# 03-MCU_INTERFACE.net
KiCad netlist of a schematic drawn in Altium Designer
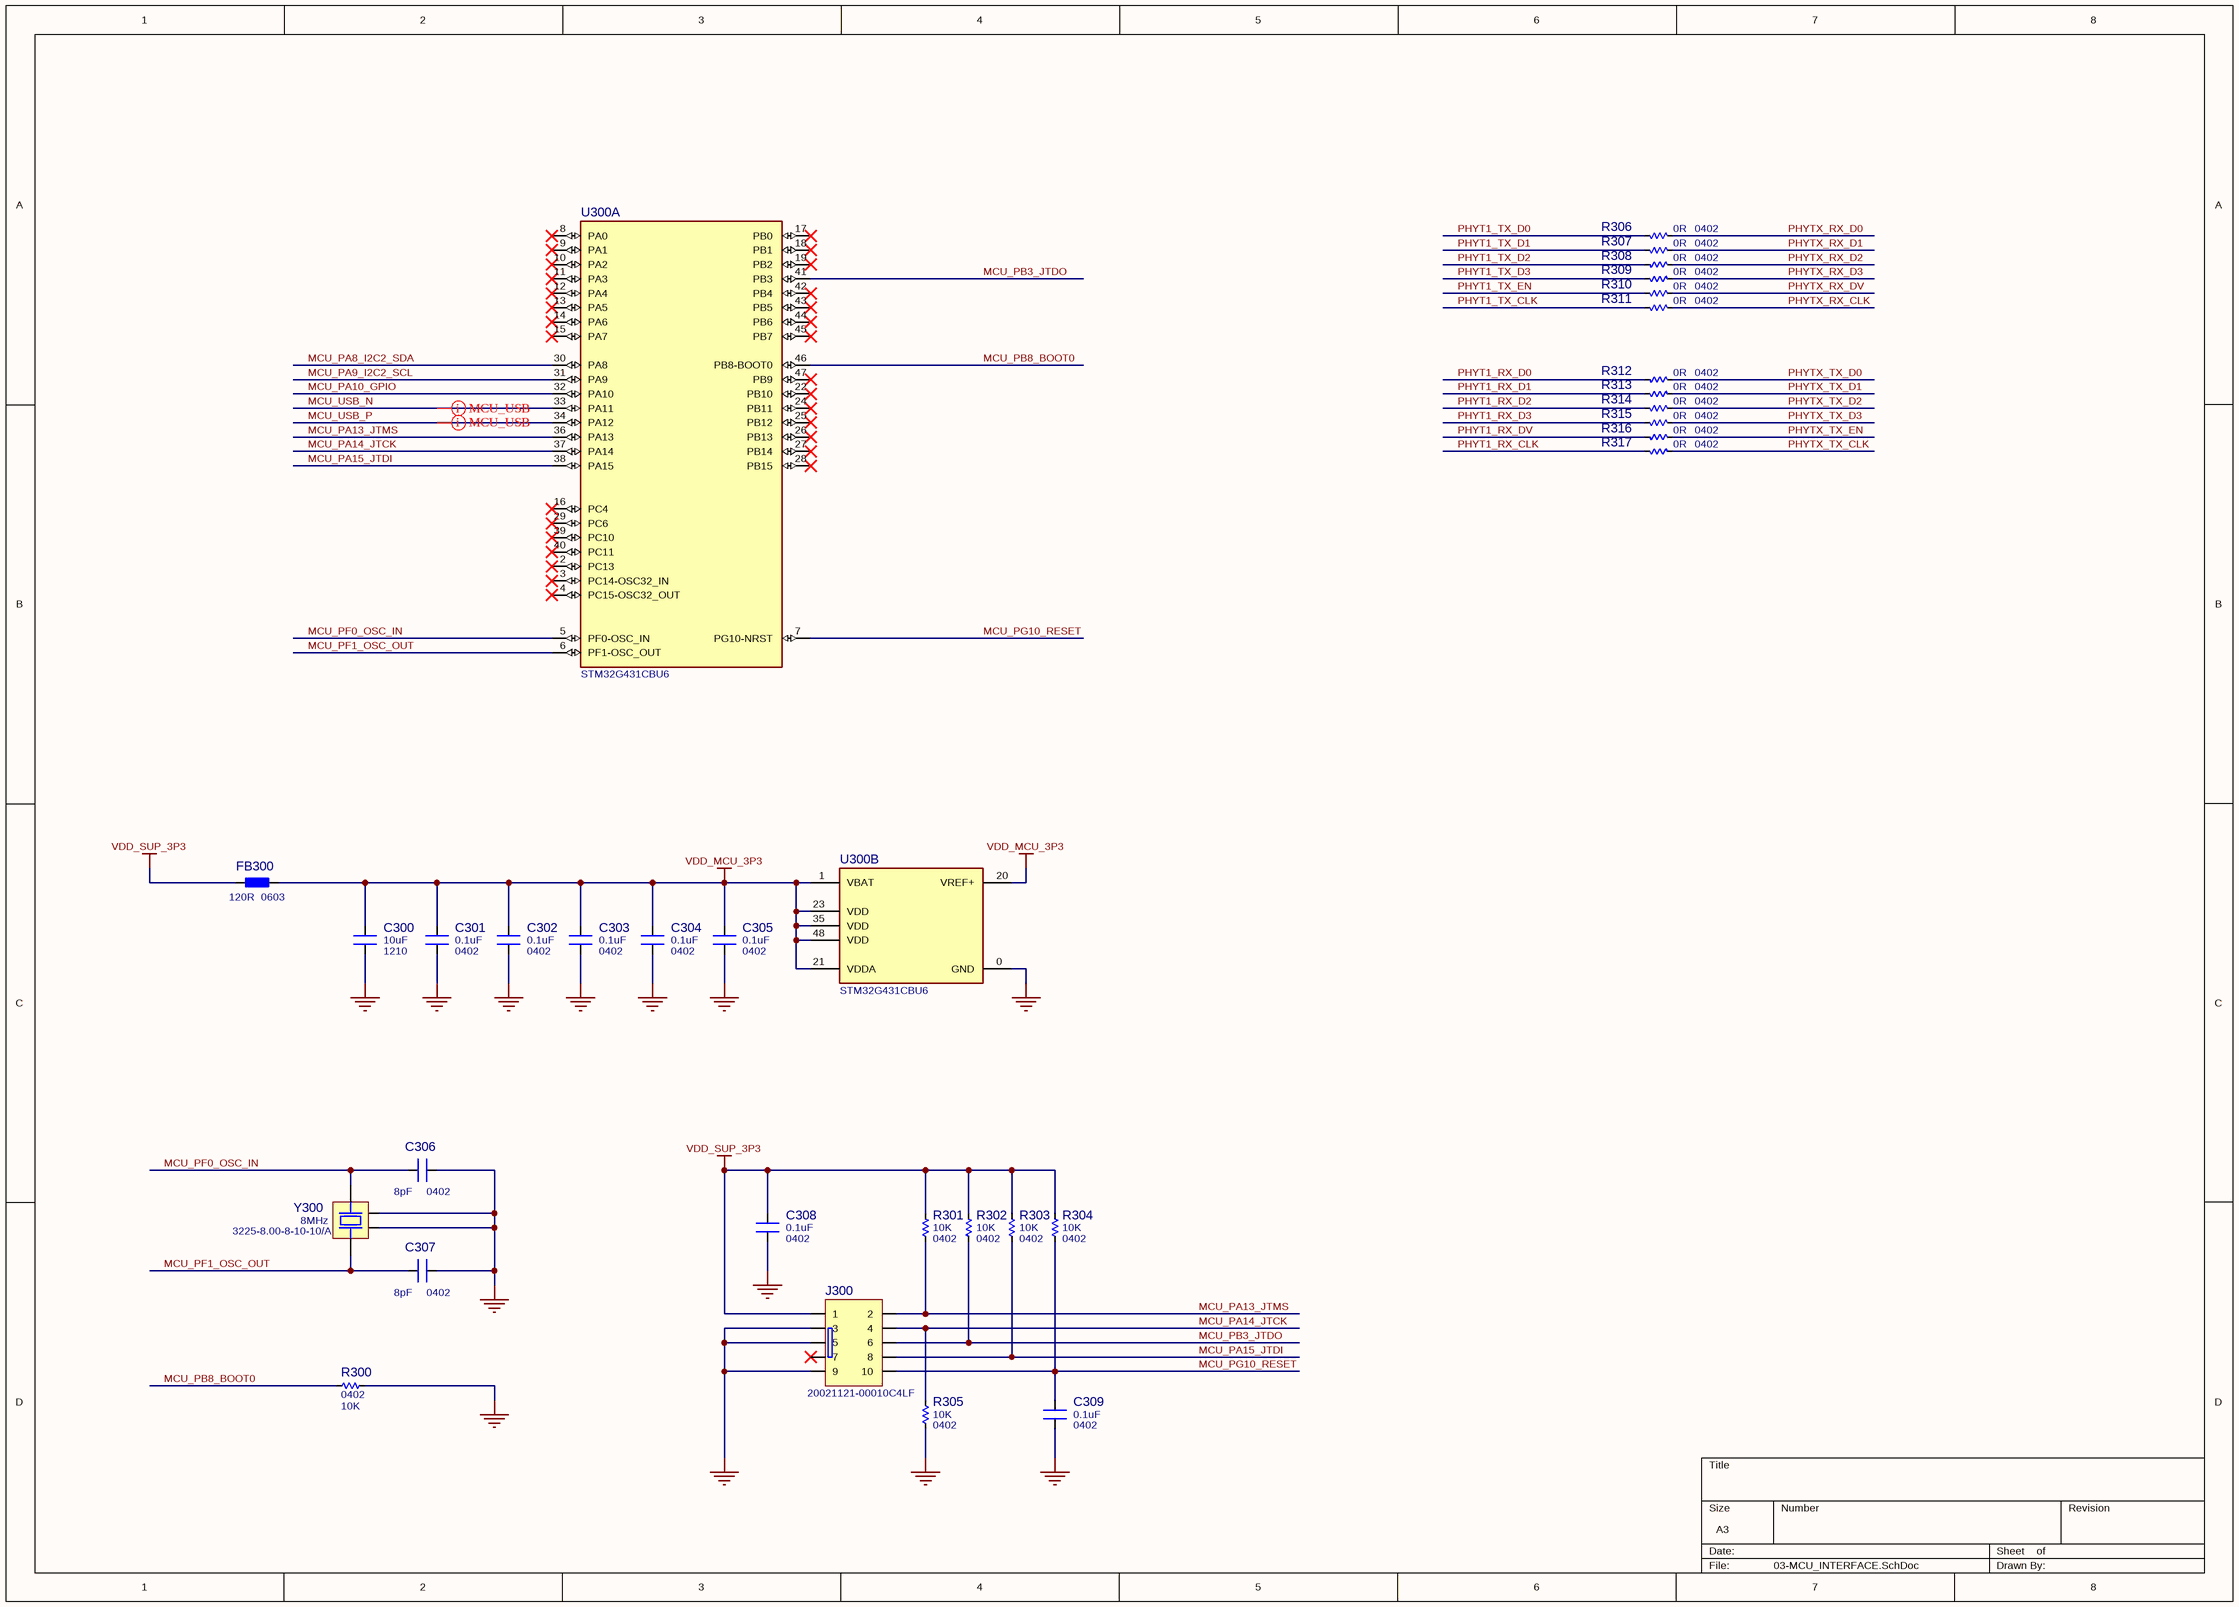
[diagram p0: 03-MCU_INTERFACE.SchDoc]

(export (version "E")
  (design (tool "Eeschema 10.0.6"))
  (components
    (comp (ref "C300")
      (value "10uF")
      (footprint "CAP_C_1210")
      (description "Ceramic Capacitor SMD 1210 10uF ±10% 25V")
      (fields
        (field (name "TOLERANCE") "±10%")
        (field (name "MANUFACTURER") "Samsung")
        (field (name "PACKAGE") "1210")
      )
      (libsource (lib "AS50") (part "Cap"))
    )
    (comp (ref "C301")
      (value "0.1uF")
      (footprint "CAP_C_0402")
      (description "Ceramic Capacitor SMD 0402 100nF ±10% 16V")
      (fields
        (field (name "TOLERANCE") "±10%")
        (field (name "MANUFACTURER") "Samsung")
        (field (name "PACKAGE") "0402")
      )
      (libsource (lib "AS50") (part "Cap"))
    )
    (comp (ref "C302")
      (value "0.1uF")
      (footprint "CAP_C_0402")
      (description "Ceramic Capacitor SMD 0402 100nF ±10% 16V")
      (fields
        (field (name "TOLERANCE") "±10%")
        (field (name "MANUFACTURER") "Samsung")
        (field (name "PACKAGE") "0402")
      )
      (libsource (lib "AS50") (part "Cap"))
    )
    (comp (ref "C303")
      (value "0.1uF")
      (footprint "CAP_C_0402")
      (description "Ceramic Capacitor SMD 0402 100nF ±10% 16V")
      (fields
        (field (name "TOLERANCE") "±10%")
        (field (name "MANUFACTURER") "Samsung")
        (field (name "PACKAGE") "0402")
      )
      (libsource (lib "AS50") (part "Cap"))
    )
    (comp (ref "C304")
      (value "0.1uF")
      (footprint "CAP_C_0402")
      (description "Ceramic Capacitor SMD 0402 100nF ±10% 16V")
      (fields
        (field (name "TOLERANCE") "±10%")
        (field (name "MANUFACTURER") "Samsung")
        (field (name "PACKAGE") "0402")
      )
      (libsource (lib "AS50") (part "Cap"))
    )
    (comp (ref "C305")
      (value "0.1uF")
      (footprint "CAP_C_0402")
      (description "Ceramic Capacitor SMD 0402 100nF ±10% 16V")
      (fields
        (field (name "TOLERANCE") "±10%")
        (field (name "MANUFACTURER") "Samsung")
        (field (name "PACKAGE") "0402")
      )
      (libsource (lib "AS50") (part "Cap"))
    )
    (comp (ref "C306")
      (value "8pF")
      (footprint "CAP_C_0402")
      (description "Ceramic Capacitor SMD 0402 8pF ±0.25pF 50V")
      (fields
        (field (name "TOLERANCE") "±0.25pF")
        (field (name "MANUFACTURER") "Yageo")
        (field (name "PACKAGE") "0402")
      )
      (libsource (lib "AS50") (part "Cap"))
    )
    (comp (ref "C307")
      (value "8pF")
      (footprint "CAP_C_0402")
      (description "Ceramic Capacitor SMD 0402 8pF ±0.25pF 50V")
      (fields
        (field (name "TOLERANCE") "±0.25pF")
        (field (name "MANUFACTURER") "Yageo")
        (field (name "PACKAGE") "0402")
      )
      (libsource (lib "AS50") (part "Cap"))
    )
    (comp (ref "C308")
      (value "0.1uF")
      (footprint "CAP_C_0402")
      (description "Ceramic Capacitor SMD 0402 100nF ±10% 16V")
      (fields
        (field (name "TOLERANCE") "±10%")
        (field (name "MANUFACTURER") "Samsung")
        (field (name "PACKAGE") "0402")
      )
      (libsource (lib "AS50") (part "Cap"))
    )
    (comp (ref "C309")
      (value "0.1uF")
      (footprint "CAP_C_0402")
      (description "Ceramic Capacitor SMD 0402 100nF ±10% 16V")
      (fields
        (field (name "TOLERANCE") "±10%")
        (field (name "MANUFACTURER") "Samsung")
        (field (name "PACKAGE") "0402")
      )
      (libsource (lib "AS50") (part "Cap"))
    )
    (comp (ref "FB300")
      (value "120R")
      (footprint "Inductors:IND_C_0603")
      (description "Ferrite bead SMD 0603 120Ω ±25% @ 100MHz DCR=0.03Ω 3A")
      (fields
        (field (name "MANUFACTURER") "Murata Electronics")
        (field (name "MANUFACTURER PART NUMBER") "BLM18KG121TH1D")
        (field (name "PACKAGE") "0603")
      )
      (libsource (lib "AS50") (part "Ferrite bead"))
    )
    (comp (ref "J300")
      (value "IDE_10P")
      (footprint "IDE_1.27-SMD-10V_2")
      (description "Conn Unshrouded Header HDR 10 POS 1.27mm Solder ST Top Entry SMD Tube")
      (fields
        (field (name "MANUFACTURER") "Amphenol ICC")
        (field (name "MANUFACTURER PART NUMBER") "20021121-00010C4LF")
      )
      (libsource (lib "AS50") (part "IDE_10P"))
    )
    (comp (ref "R300")
      (value "10K")
      (footprint "RES_C_0402")
      (description "Resistor SMD 0402 10K ±1% 1/16W")
      (fields (field (name "PACKAGE") "0402") (field (name "TOLERANCE") "±1%") (field (name "VOLTAGE") "50V"))
      (libsource (lib "AS50") (part "Res"))
    )
    (comp (ref "R301")
      (value "10K")
      (footprint "RES_C_0402")
      (description "Resistor SMD 0402 10K ±1% 1/16W")
      (fields (field (name "PACKAGE") "0402") (field (name "TOLERANCE") "±1%") (field (name "VOLTAGE") "50V"))
      (libsource (lib "AS50") (part "Res"))
    )
    (comp (ref "R302")
      (value "10K")
      (footprint "RES_C_0402")
      (description "Resistor SMD 0402 10K ±1% 1/16W")
      (fields (field (name "PACKAGE") "0402") (field (name "TOLERANCE") "±1%") (field (name "VOLTAGE") "50V"))
      (libsource (lib "AS50") (part "Res"))
    )
    (comp (ref "R303")
      (value "10K")
      (footprint "RES_C_0402")
      (description "Resistor SMD 0402 10K ±1% 1/16W")
      (fields (field (name "PACKAGE") "0402") (field (name "TOLERANCE") "±1%") (field (name "VOLTAGE") "50V"))
      (libsource (lib "AS50") (part "Res"))
    )
    (comp (ref "R304")
      (value "10K")
      (footprint "RES_C_0402")
      (description "Resistor SMD 0402 10K ±1% 1/16W")
      (fields (field (name "PACKAGE") "0402") (field (name "TOLERANCE") "±1%") (field (name "VOLTAGE") "50V"))
      (libsource (lib "AS50") (part "Res"))
    )
    (comp (ref "R305")
      (value "10K")
      (footprint "RES_C_0402")
      (description "Resistor SMD 0402 10K ±1% 1/16W")
      (fields (field (name "PACKAGE") "0402") (field (name "TOLERANCE") "±1%") (field (name "VOLTAGE") "50V"))
      (libsource (lib "AS50") (part "Res"))
    )
    (comp (ref "R306")
      (value "0R")
      (footprint "RES_C_0402")
      (description "Resistor SMD 0402 0R ±1% 1/16W")
      (fields (field (name "PACKAGE") "0402") (field (name "TOLERANCE") "±1%") (field (name "VOLTAGE") "50V"))
      (libsource (lib "AS50") (part "Res"))
    )
    (comp (ref "R307")
      (value "0R")
      (footprint "RES_C_0402")
      (description "Resistor SMD 0402 0R ±1% 1/16W")
      (fields (field (name "PACKAGE") "0402") (field (name "TOLERANCE") "±1%") (field (name "VOLTAGE") "50V"))
      (libsource (lib "AS50") (part "Res"))
    )
    (comp (ref "R308")
      (value "0R")
      (footprint "RES_C_0402")
      (description "Resistor SMD 0402 0R ±1% 1/16W")
      (fields (field (name "PACKAGE") "0402") (field (name "TOLERANCE") "±1%") (field (name "VOLTAGE") "50V"))
      (libsource (lib "AS50") (part "Res"))
    )
    (comp (ref "R309")
      (value "0R")
      (footprint "RES_C_0402")
      (description "Resistor SMD 0402 0R ±1% 1/16W")
      (fields (field (name "PACKAGE") "0402") (field (name "TOLERANCE") "±1%") (field (name "VOLTAGE") "50V"))
      (libsource (lib "AS50") (part "Res"))
    )
    (comp (ref "R310")
      (value "0R")
      (footprint "RES_C_0402")
      (description "Resistor SMD 0402 0R ±1% 1/16W")
      (fields (field (name "PACKAGE") "0402") (field (name "TOLERANCE") "±1%") (field (name "VOLTAGE") "50V"))
      (libsource (lib "AS50") (part "Res"))
    )
    (comp (ref "R311")
      (value "0R")
      (footprint "RES_C_0402")
      (description "Resistor SMD 0402 0R ±1% 1/16W")
      (fields (field (name "PACKAGE") "0402") (field (name "TOLERANCE") "±1%") (field (name "VOLTAGE") "50V"))
      (libsource (lib "AS50") (part "Res"))
    )
    (comp (ref "R312")
      (value "0R")
      (footprint "RES_C_0402")
      (description "Resistor SMD 0402 0R ±1% 1/16W")
      (fields (field (name "PACKAGE") "0402") (field (name "TOLERANCE") "±1%") (field (name "VOLTAGE") "50V"))
      (libsource (lib "AS50") (part "Res"))
    )
    (comp (ref "R313")
      (value "0R")
      (footprint "RES_C_0402")
      (description "Resistor SMD 0402 0R ±1% 1/16W")
      (fields (field (name "PACKAGE") "0402") (field (name "TOLERANCE") "±1%") (field (name "VOLTAGE") "50V"))
      (libsource (lib "AS50") (part "Res"))
    )
    (comp (ref "R314")
      (value "0R")
      (footprint "RES_C_0402")
      (description "Resistor SMD 0402 0R ±1% 1/16W")
      (fields (field (name "PACKAGE") "0402") (field (name "TOLERANCE") "±1%") (field (name "VOLTAGE") "50V"))
      (libsource (lib "AS50") (part "Res"))
    )
    (comp (ref "R315")
      (value "0R")
      (footprint "RES_C_0402")
      (description "Resistor SMD 0402 0R ±1% 1/16W")
      (fields (field (name "PACKAGE") "0402") (field (name "TOLERANCE") "±1%") (field (name "VOLTAGE") "50V"))
      (libsource (lib "AS50") (part "Res"))
    )
    (comp (ref "R316")
      (value "0R")
      (footprint "RES_C_0402")
      (description "Resistor SMD 0402 0R ±1% 1/16W")
      (fields (field (name "PACKAGE") "0402") (field (name "TOLERANCE") "±1%") (field (name "VOLTAGE") "50V"))
      (libsource (lib "AS50") (part "Res"))
    )
    (comp (ref "R317")
      (value "0R")
      (footprint "RES_C_0402")
      (description "Resistor SMD 0402 0R ±1% 1/16W")
      (fields (field (name "PACKAGE") "0402") (field (name "TOLERANCE") "±1%") (field (name "VOLTAGE") "50V"))
      (libsource (lib "AS50") (part "Res"))
    )
    (comp (ref "U300")
      (value "STM32G431CBU6")
      (footprint "QFN50P700X700X100_HS-49N")
      (fields
        (field (name "MANUFACTURER") "STMicroelectronics")
        (field (name "MANUFACTURER PART NUMBER") "STM32G431CBU6")
      )
      (libsource (lib "AS50") (part "STM32G431CBU6"))
    )
    (comp (ref "Y300")
      (value "Crystal")
      (footprint "XT-SMD-3225-4P")
      (description "8MHz SMD Crystal Resonator 8pF ±10ppm ±20ppm -20℃~+70℃ SMD3225-4P")
      (fields
        (field (name "MANUFACTURER") "Suzhou Liming Elec")
        (field (name "MANUFACTURER PART NUMBER") "3225-8.00-8-10-10/A")
        (field (name "FREQUENCY") "8MHz")
      )
      (libsource (lib "AS50") (part "CX3225SB12000H0PSTC1"))
    )
  )
  (nets
    (net (code "1") (name "/MCU_PA8_I2C2_SDA") (class "Default")
      (node (ref "U300") (pin "30") (pinfunction "PA8_30") (pintype "bidirectional"))
    )
    (net (code "2") (name "/MCU_PA9_I2C2_SCL") (class "Default")
      (node (ref "U300") (pin "31") (pinfunction "PA9_31") (pintype "bidirectional"))
    )
    (net (code "3") (name "/MCU_PA10_GPIO") (class "Default")
      (node (ref "U300") (pin "32") (pinfunction "PA10_32") (pintype "bidirectional"))
    )
    (net (code "4") (name "/MCU_PA13_JTMS") (class "Default")
      (node (ref "J300") (pin "2") (pinfunction "2_2") (pintype "passive"))
      (node (ref "R301") (pin "2") (pinfunction "2_2") (pintype "passive"))
      (node (ref "U300") (pin "36") (pinfunction "PA13_36") (pintype "bidirectional"))
    )
    (net (code "5") (name "/MCU_PA14_JTCK") (class "Default")
      (node (ref "J300") (pin "4") (pinfunction "4_4") (pintype "passive"))
      (node (ref "R305") (pin "1") (pinfunction "1_1") (pintype "passive"))
      (node (ref "U300") (pin "37") (pinfunction "PA14_37") (pintype "bidirectional"))
    )
    (net (code "6") (name "/MCU_PA15_JTDI") (class "Default")
      (node (ref "J300") (pin "8") (pinfunction "8_8") (pintype "passive"))
      (node (ref "R303") (pin "2") (pinfunction "2_2") (pintype "passive"))
      (node (ref "U300") (pin "38") (pinfunction "PA15_38") (pintype "bidirectional"))
    )
    (net (code "7") (name "/MCU_PB3_JTDO") (class "Default")
      (node (ref "J300") (pin "6") (pinfunction "6_6") (pintype "passive"))
      (node (ref "R302") (pin "2") (pinfunction "2_2") (pintype "passive"))
      (node (ref "U300") (pin "41") (pinfunction "PB3_41") (pintype "bidirectional"))
    )
    (net (code "8") (name "/MCU_PB8_BOOT0") (class "Default")
      (node (ref "R300") (pin "1") (pinfunction "1_1") (pintype "passive"))
      (node (ref "U300") (pin "46") (pinfunction "PB8-BOOT0_46") (pintype "bidirectional"))
    )
    (net (code "9") (name "/MCU_PF0_OSC_IN") (class "Default")
      (node (ref "C306") (pin "2") (pinfunction "2_2") (pintype "passive"))
      (node (ref "U300") (pin "5") (pinfunction "PF0-OSC_IN_5") (pintype "bidirectional"))
      (node (ref "Y300") (pin "1") (pinfunction "1_1") (pintype "passive"))
    )
    (net (code "10") (name "/MCU_PF1_OSC_OUT") (class "Default")
      (node (ref "C307") (pin "2") (pinfunction "2_2") (pintype "passive"))
      (node (ref "U300") (pin "6") (pinfunction "PF1-OSC_OUT_6") (pintype "bidirectional"))
      (node (ref "Y300") (pin "3") (pinfunction "3_3") (pintype "passive"))
    )
    (net (code "11") (name "/MCU_PG10_RESET") (class "Default")
      (node (ref "C309") (pin "2") (pinfunction "2_2") (pintype "passive"))
      (node (ref "J300") (pin "10") (pinfunction "10_10") (pintype "passive"))
      (node (ref "R304") (pin "2") (pinfunction "2_2") (pintype "passive"))
      (node (ref "U300") (pin "7") (pinfunction "PG10-NRST_7") (pintype "bidirectional"))
    )
    (net (code "12") (name "/MCU_USB_N") (class "Default")
      (node (ref "U300") (pin "33") (pinfunction "PA11_33") (pintype "bidirectional"))
    )
    (net (code "13") (name "/MCU_USB_P") (class "Default")
      (node (ref "U300") (pin "34") (pinfunction "PA12_34") (pintype "bidirectional"))
    )
    (net (code "14") (name "/PHYT1_RX_CLK") (class "Default")
      (node (ref "R317") (pin "2") (pinfunction "2_2") (pintype "passive"))
    )
    (net (code "15") (name "/PHYT1_RX_D0") (class "Default")
      (node (ref "R312") (pin "2") (pinfunction "2_2") (pintype "passive"))
    )
    (net (code "16") (name "/PHYT1_RX_D1") (class "Default")
      (node (ref "R313") (pin "2") (pinfunction "2_2") (pintype "passive"))
    )
    (net (code "17") (name "/PHYT1_RX_D2") (class "Default")
      (node (ref "R314") (pin "2") (pinfunction "2_2") (pintype "passive"))
    )
    (net (code "18") (name "/PHYT1_RX_D3") (class "Default")
      (node (ref "R315") (pin "2") (pinfunction "2_2") (pintype "passive"))
    )
    (net (code "19") (name "/PHYT1_RX_DV") (class "Default")
      (node (ref "R316") (pin "2") (pinfunction "2_2") (pintype "passive"))
    )
    (net (code "20") (name "/PHYT1_TX_CLK") (class "Default")
      (node (ref "R311") (pin "2") (pinfunction "2_2") (pintype "passive"))
    )
    (net (code "21") (name "/PHYT1_TX_D0") (class "Default")
      (node (ref "R306") (pin "2") (pinfunction "2_2") (pintype "passive"))
    )
    (net (code "22") (name "/PHYT1_TX_D1") (class "Default")
      (node (ref "R307") (pin "2") (pinfunction "2_2") (pintype "passive"))
    )
    (net (code "23") (name "/PHYT1_TX_D2") (class "Default")
      (node (ref "R308") (pin "2") (pinfunction "2_2") (pintype "passive"))
    )
    (net (code "24") (name "/PHYT1_TX_D3") (class "Default")
      (node (ref "R309") (pin "2") (pinfunction "2_2") (pintype "passive"))
    )
    (net (code "25") (name "/PHYT1_TX_EN") (class "Default")
      (node (ref "R310") (pin "2") (pinfunction "2_2") (pintype "passive"))
    )
    (net (code "26") (name "/PHYTX_RX_CLK") (class "Default")
      (node (ref "R311") (pin "1") (pinfunction "1_1") (pintype "passive"))
    )
    (net (code "27") (name "/PHYTX_RX_D0") (class "Default")
      (node (ref "R306") (pin "1") (pinfunction "1_1") (pintype "passive"))
    )
    (net (code "28") (name "/PHYTX_RX_D1") (class "Default")
      (node (ref "R307") (pin "1") (pinfunction "1_1") (pintype "passive"))
    )
    (net (code "29") (name "/PHYTX_RX_D2") (class "Default")
      (node (ref "R308") (pin "1") (pinfunction "1_1") (pintype "passive"))
    )
    (net (code "30") (name "/PHYTX_RX_D3") (class "Default")
      (node (ref "R309") (pin "1") (pinfunction "1_1") (pintype "passive"))
    )
    (net (code "31") (name "/PHYTX_RX_DV") (class "Default")
      (node (ref "R310") (pin "1") (pinfunction "1_1") (pintype "passive"))
    )
    (net (code "32") (name "/PHYTX_TX_CLK") (class "Default")
      (node (ref "R317") (pin "1") (pinfunction "1_1") (pintype "passive"))
    )
    (net (code "33") (name "/PHYTX_TX_D0") (class "Default")
      (node (ref "R312") (pin "1") (pinfunction "1_1") (pintype "passive"))
    )
    (net (code "34") (name "/PHYTX_TX_D1") (class "Default")
      (node (ref "R313") (pin "1") (pinfunction "1_1") (pintype "passive"))
    )
    (net (code "35") (name "/PHYTX_TX_D2") (class "Default")
      (node (ref "R314") (pin "1") (pinfunction "1_1") (pintype "passive"))
    )
    (net (code "36") (name "/PHYTX_TX_D3") (class "Default")
      (node (ref "R315") (pin "1") (pinfunction "1_1") (pintype "passive"))
    )
    (net (code "37") (name "/PHYTX_TX_EN") (class "Default")
      (node (ref "R316") (pin "1") (pinfunction "1_1") (pintype "passive"))
    )
    (net (code "38") (name "GND") (class "Default")
      (node (ref "C300") (pin "1") (pinfunction "1_1") (pintype "passive"))
      (node (ref "C301") (pin "1") (pinfunction "1_1") (pintype "passive"))
      (node (ref "C302") (pin "1") (pinfunction "1_1") (pintype "passive"))
      (node (ref "C303") (pin "1") (pinfunction "1_1") (pintype "passive"))
      (node (ref "C304") (pin "1") (pinfunction "1_1") (pintype "passive"))
      (node (ref "C305") (pin "1") (pinfunction "1_1") (pintype "passive"))
      (node (ref "C306") (pin "1") (pinfunction "1_1") (pintype "passive"))
      (node (ref "C307") (pin "1") (pinfunction "1_1") (pintype "passive"))
      (node (ref "C308") (pin "1") (pinfunction "1_1") (pintype "passive"))
      (node (ref "C309") (pin "1") (pinfunction "1_1") (pintype "passive"))
      (node (ref "J300") (pin "3") (pinfunction "3_3") (pintype "passive"))
      (node (ref "J300") (pin "5") (pinfunction "5_5") (pintype "passive"))
      (node (ref "J300") (pin "9") (pinfunction "9_9") (pintype "passive"))
      (node (ref "R300") (pin "2") (pinfunction "2_2") (pintype "passive"))
      (node (ref "R305") (pin "2") (pinfunction "2_2") (pintype "passive"))
      (node (ref "U300") (pin "0") (pinfunction "GND_0") (pintype "passive"))
      (node (ref "Y300") (pin "2") (pinfunction "2_2") (pintype "power_in"))
      (node (ref "Y300") (pin "4") (pinfunction "4_4") (pintype "power_in"))
    )
    (net (code "39") (name "VDD_MCU_3P3") (class "Default")
      (node (ref "C300") (pin "2") (pinfunction "2_2") (pintype "passive"))
      (node (ref "C301") (pin "2") (pinfunction "2_2") (pintype "passive"))
      (node (ref "C302") (pin "2") (pinfunction "2_2") (pintype "passive"))
      (node (ref "C303") (pin "2") (pinfunction "2_2") (pintype "passive"))
      (node (ref "C304") (pin "2") (pinfunction "2_2") (pintype "passive"))
      (node (ref "C305") (pin "2") (pinfunction "2_2") (pintype "passive"))
      (node (ref "FB300") (pin "1") (pinfunction "1_1") (pintype "passive"))
      (node (ref "U300") (pin "1") (pinfunction "VBAT_1") (pintype "power_in"))
      (node (ref "U300") (pin "20") (pinfunction "VREF+_20") (pintype "power_in"))
      (node (ref "U300") (pin "21") (pinfunction "VDDA_21") (pintype "power_in"))
      (node (ref "U300") (pin "23") (pinfunction "VDD_23") (pintype "power_in"))
      (node (ref "U300") (pin "35") (pinfunction "VDD_35") (pintype "power_in"))
      (node (ref "U300") (pin "48") (pinfunction "VDD_48") (pintype "power_in"))
    )
    (net (code "40") (name "VDD_SUP_3P3") (class "Default")
      (node (ref "C308") (pin "2") (pinfunction "2_2") (pintype "passive"))
      (node (ref "FB300") (pin "2") (pinfunction "2_2") (pintype "passive"))
      (node (ref "J300") (pin "1") (pinfunction "1_1") (pintype "passive"))
      (node (ref "R301") (pin "1") (pinfunction "1_1") (pintype "passive"))
      (node (ref "R302") (pin "1") (pinfunction "1_1") (pintype "passive"))
      (node (ref "R303") (pin "1") (pinfunction "1_1") (pintype "passive"))
      (node (ref "R304") (pin "1") (pinfunction "1_1") (pintype "passive"))
    )
    (net (code "41") (name "unconnected-(J300-Pad7)") (class "Default")
      (node (ref "J300") (pin "7") (pinfunction "7_7") (pintype "passive+no_connect"))
    )
    (net (code "42") (name "unconnected-(U300A-PA0-Pad8)") (class "Default")
      (node (ref "U300") (pin "8") (pinfunction "PA0_8") (pintype "bidirectional+no_connect"))
    )
    (net (code "43") (name "unconnected-(U300A-PA1-Pad9)") (class "Default")
      (node (ref "U300") (pin "9") (pinfunction "PA1_9") (pintype "bidirectional+no_connect"))
    )
    (net (code "44") (name "unconnected-(U300A-PA2-Pad10)") (class "Default")
      (node (ref "U300") (pin "10") (pinfunction "PA2_10") (pintype "bidirectional+no_connect"))
    )
    (net (code "45") (name "unconnected-(U300A-PA3-Pad11)") (class "Default")
      (node (ref "U300") (pin "11") (pinfunction "PA3_11") (pintype "bidirectional+no_connect"))
    )
    (net (code "46") (name "unconnected-(U300A-PA4-Pad12)") (class "Default")
      (node (ref "U300") (pin "12") (pinfunction "PA4_12") (pintype "bidirectional+no_connect"))
    )
    (net (code "47") (name "unconnected-(U300A-PA5-Pad13)") (class "Default")
      (node (ref "U300") (pin "13") (pinfunction "PA5_13") (pintype "bidirectional+no_connect"))
    )
    (net (code "48") (name "unconnected-(U300A-PA6-Pad14)") (class "Default")
      (node (ref "U300") (pin "14") (pinfunction "PA6_14") (pintype "bidirectional+no_connect"))
    )
    (net (code "49") (name "unconnected-(U300A-PA7-Pad15)") (class "Default")
      (node (ref "U300") (pin "15") (pinfunction "PA7_15") (pintype "bidirectional+no_connect"))
    )
    (net (code "50") (name "unconnected-(U300A-PB0-Pad17)") (class "Default")
      (node (ref "U300") (pin "17") (pinfunction "PB0_17") (pintype "bidirectional+no_connect"))
    )
    (net (code "51") (name "unconnected-(U300A-PB1-Pad18)") (class "Default")
      (node (ref "U300") (pin "18") (pinfunction "PB1_18") (pintype "bidirectional+no_connect"))
    )
    (net (code "52") (name "unconnected-(U300A-PB2-Pad19)") (class "Default")
      (node (ref "U300") (pin "19") (pinfunction "PB2_19") (pintype "bidirectional+no_connect"))
    )
    (net (code "53") (name "unconnected-(U300A-PB4-Pad42)") (class "Default")
      (node (ref "U300") (pin "42") (pinfunction "PB4_42") (pintype "bidirectional+no_connect"))
    )
    (net (code "54") (name "unconnected-(U300A-PB5-Pad43)") (class "Default")
      (node (ref "U300") (pin "43") (pinfunction "PB5_43") (pintype "bidirectional+no_connect"))
    )
    (net (code "55") (name "unconnected-(U300A-PB6-Pad44)") (class "Default")
      (node (ref "U300") (pin "44") (pinfunction "PB6_44") (pintype "bidirectional+no_connect"))
    )
    (net (code "56") (name "unconnected-(U300A-PB7-Pad45)") (class "Default")
      (node (ref "U300") (pin "45") (pinfunction "PB7_45") (pintype "bidirectional+no_connect"))
    )
    (net (code "57") (name "unconnected-(U300A-PB9-Pad47)") (class "Default")
      (node (ref "U300") (pin "47") (pinfunction "PB9_47") (pintype "bidirectional+no_connect"))
    )
    (net (code "58") (name "unconnected-(U300A-PB10-Pad22)") (class "Default")
      (node (ref "U300") (pin "22") (pinfunction "PB10_22") (pintype "bidirectional+no_connect"))
    )
    (net (code "59") (name "unconnected-(U300A-PB11-Pad24)") (class "Default")
      (node (ref "U300") (pin "24") (pinfunction "PB11_24") (pintype "bidirectional+no_connect"))
    )
    (net (code "60") (name "unconnected-(U300A-PB12-Pad25)") (class "Default")
      (node (ref "U300") (pin "25") (pinfunction "PB12_25") (pintype "bidirectional+no_connect"))
    )
    (net (code "61") (name "unconnected-(U300A-PB13-Pad26)") (class "Default")
      (node (ref "U300") (pin "26") (pinfunction "PB13_26") (pintype "bidirectional+no_connect"))
    )
    (net (code "62") (name "unconnected-(U300A-PB14-Pad27)") (class "Default")
      (node (ref "U300") (pin "27") (pinfunction "PB14_27") (pintype "bidirectional+no_connect"))
    )
    (net (code "63") (name "unconnected-(U300A-PB15-Pad28)") (class "Default")
      (node (ref "U300") (pin "28") (pinfunction "PB15_28") (pintype "bidirectional+no_connect"))
    )
    (net (code "64") (name "unconnected-(U300A-PC4-Pad16)") (class "Default")
      (node (ref "U300") (pin "16") (pinfunction "PC4_16") (pintype "bidirectional+no_connect"))
    )
    (net (code "65") (name "unconnected-(U300A-PC6-Pad29)") (class "Default")
      (node (ref "U300") (pin "29") (pinfunction "PC6_29") (pintype "bidirectional+no_connect"))
    )
    (net (code "66") (name "unconnected-(U300A-PC10-Pad39)") (class "Default")
      (node (ref "U300") (pin "39") (pinfunction "PC10_39") (pintype "bidirectional+no_connect"))
    )
    (net (code "67") (name "unconnected-(U300A-PC11-Pad40)") (class "Default")
      (node (ref "U300") (pin "40") (pinfunction "PC11_40") (pintype "bidirectional+no_connect"))
    )
    (net (code "68") (name "unconnected-(U300A-PC13-Pad2)") (class "Default")
      (node (ref "U300") (pin "2") (pinfunction "PC13_2") (pintype "bidirectional+no_connect"))
    )
    (net (code "69") (name "unconnected-(U300A-PC14-OSC32_IN-Pad3)") (class "Default")
      (node (ref "U300") (pin "3") (pinfunction "PC14-OSC32_IN_3") (pintype "bidirectional+no_connect"))
    )
    (net (code "70") (name "unconnected-(U300A-PC15-OSC32_OUT-Pad4)") (class "Default")
      (node (ref "U300") (pin "4") (pinfunction "PC15-OSC32_OUT_4") (pintype "bidirectional+no_connect"))
    )
  )
)
